# L289.net
KiCad netlist of a schematic drawn in EAGLE
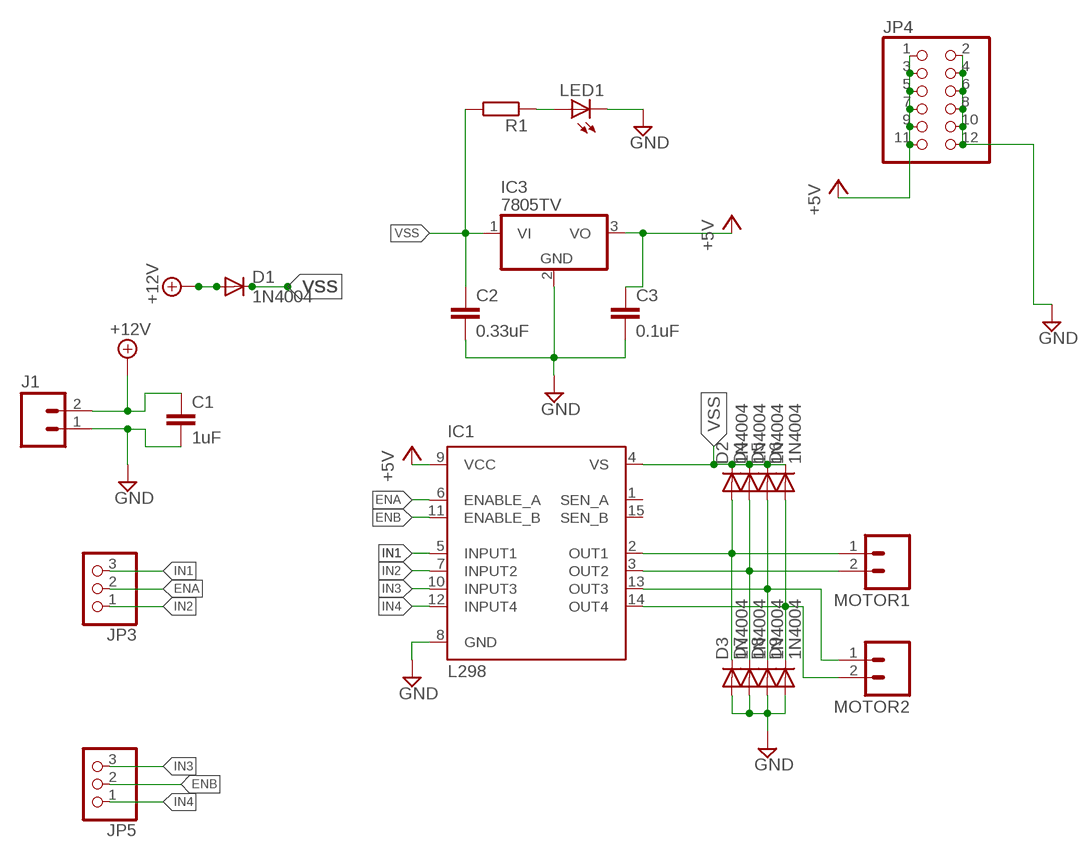
[diagram p0: schematic, sheet 1]

(export (version "E")
  (design (tool "Eeschema 10.0.6"))
  (components
    (comp (ref "C1")
      (value "1uF")
      (footprint "eagle-import:C050-024X044")
      (libsource (lib "eagle-import") (part "C-EU050-024X044"))
    )
    (comp (ref "C2")
      (value "0.33uF")
      (footprint "eagle-import:C050-024X044")
      (libsource (lib "eagle-import") (part "C-EU050-024X044"))
    )
    (comp (ref "C3")
      (value "0.1uF")
      (footprint "eagle-import:C050-024X044")
      (libsource (lib "eagle-import") (part "C-EU050-024X044"))
    )
    (comp (ref "D1")
      (value "1N4004")
      (footprint "eagle-import:DO41-10")
      (libsource (lib "eagle-import") (part "1N4004"))
    )
    (comp (ref "D2")
      (value "1N4004")
      (footprint "eagle-import:DO41-10")
      (libsource (lib "eagle-import") (part "1N4004"))
    )
    (comp (ref "D3")
      (value "1N4004")
      (footprint "eagle-import:DO41-10")
      (libsource (lib "eagle-import") (part "1N4004"))
    )
    (comp (ref "D4")
      (value "1N4004")
      (footprint "eagle-import:DO41-10")
      (libsource (lib "eagle-import") (part "1N4004"))
    )
    (comp (ref "D5")
      (value "1N4004")
      (footprint "eagle-import:DO41-10")
      (libsource (lib "eagle-import") (part "1N4004"))
    )
    (comp (ref "D6")
      (value "1N4004")
      (footprint "eagle-import:DO41-10")
      (libsource (lib "eagle-import") (part "1N4004"))
    )
    (comp (ref "D7")
      (value "1N4004")
      (footprint "eagle-import:DO41-10")
      (libsource (lib "eagle-import") (part "1N4004"))
    )
    (comp (ref "D8")
      (value "1N4004")
      (footprint "eagle-import:DO41-10")
      (libsource (lib "eagle-import") (part "1N4004"))
    )
    (comp (ref "D9")
      (value "1N4004")
      (footprint "eagle-import:DO41-10")
      (libsource (lib "eagle-import") (part "1N4004"))
    )
    (comp (ref "IC1")
      (value "L298")
      (footprint "eagle-import:MULTIWATT-15")
      (fields (field (name "MPN") "L298N"))
      (libsource (lib "eagle-import") (part "L298"))
    )
    (comp (ref "IC3")
      (value "7805TV")
      (footprint "eagle-import:TO220V")
      (libsource (lib "eagle-import") (part "78TV05"))
    )
    (comp (ref "J1")
      (value "M02-JST-2-PTH-NO_SILK")
      (footprint "eagle-import:JST-2-PTH-NS")
      (libsource (lib "eagle-import") (part "M02-JST-2-PTH-NO_SILK"))
    )
    (comp (ref "JP3")
      (value "PINHD-1X3")
      (footprint "eagle-import:1X03")
      (libsource (lib "eagle-import") (part "PINHD-1X3"))
    )
    (comp (ref "JP4")
      (value "PINHD-2X6")
      (footprint "eagle-import:2X06")
      (libsource (lib "eagle-import") (part "PINHD-2X6"))
    )
    (comp (ref "JP5")
      (value "PINHD-1X3")
      (footprint "eagle-import:1X03")
      (libsource (lib "eagle-import") (part "PINHD-1X3"))
    )
    (comp (ref "LED1")
      (value "LED3MM")
      (footprint "eagle-import:LED3MM")
      (libsource (lib "eagle-import") (part "LED3MM"))
    )
    (comp (ref "MOTOR1")
      (value "M02-JST-2-PTH-NO_SILK")
      (footprint "eagle-import:JST-2-PTH-NS")
      (libsource (lib "eagle-import") (part "M02-JST-2-PTH-NO_SILK"))
    )
    (comp (ref "MOTOR2")
      (value "M02-JST-2-PTH-NO_SILK")
      (footprint "eagle-import:JST-2-PTH-NS")
      (libsource (lib "eagle-import") (part "M02-JST-2-PTH-NO_SILK"))
    )
    (comp (ref "R1")
      (value "R-EU_0207/5V")
      (footprint "eagle-import:0207_5V")
      (libsource (lib "eagle-import") (part "R-EU_0207/5V"))
    )
  )
  (nets
    (net (code "1") (name "+5V") (class "Default")
      (node (ref "C3") (pin "1") (pinfunction "1_1") (pintype "passive"))
      (node (ref "IC1") (pin "9") (pinfunction "VCC_9") (pintype "power_in"))
      (node (ref "IC3") (pin "3") (pinfunction "VO_3") (pintype "passive"))
      (node (ref "JP4") (pin "1") (pinfunction "1_1") (pintype "passive"))
      (node (ref "JP4") (pin "11") (pinfunction "11_11") (pintype "passive"))
      (node (ref "JP4") (pin "3") (pinfunction "3_3") (pintype "passive"))
      (node (ref "JP4") (pin "5") (pinfunction "5_5") (pintype "passive"))
      (node (ref "JP4") (pin "7") (pinfunction "7_7") (pintype "passive"))
      (node (ref "JP4") (pin "9") (pinfunction "9_9") (pintype "passive"))
    )
    (net (code "2") (name "+12V") (class "Default")
      (node (ref "C1") (pin "1") (pinfunction "1_1") (pintype "passive"))
      (node (ref "D1") (pin "A") (pinfunction "A_A") (pintype "passive"))
      (node (ref "J1") (pin "2") (pinfunction "2_2") (pintype "passive"))
    )
    (net (code "3") (name "ENA") (class "Default")
      (node (ref "IC1") (pin "6") (pinfunction "ENABLE_A_6") (pintype "input"))
      (node (ref "JP3") (pin "2") (pinfunction "2_2") (pintype "passive"))
    )
    (net (code "4") (name "ENB") (class "Default")
      (node (ref "IC1") (pin "11") (pinfunction "ENABLE_B_11") (pintype "input"))
      (node (ref "JP5") (pin "2") (pinfunction "2_2") (pintype "passive"))
    )
    (net (code "5") (name "GND") (class "Default")
      (node (ref "C1") (pin "2") (pinfunction "2_2") (pintype "passive"))
      (node (ref "C2") (pin "2") (pinfunction "2_2") (pintype "passive"))
      (node (ref "C3") (pin "2") (pinfunction "2_2") (pintype "passive"))
      (node (ref "D3") (pin "A") (pinfunction "A_A") (pintype "passive"))
      (node (ref "D7") (pin "A") (pinfunction "A_A") (pintype "passive"))
      (node (ref "D8") (pin "A") (pinfunction "A_A") (pintype "passive"))
      (node (ref "D9") (pin "A") (pinfunction "A_A") (pintype "passive"))
      (node (ref "IC1") (pin "8") (pinfunction "GND_8") (pintype "power_in"))
      (node (ref "IC3") (pin "2") (pinfunction "GND_2") (pintype "passive"))
      (node (ref "J1") (pin "1") (pinfunction "1_1") (pintype "passive"))
      (node (ref "JP4") (pin "10") (pinfunction "10_10") (pintype "passive"))
      (node (ref "JP4") (pin "12") (pinfunction "12_12") (pintype "passive"))
      (node (ref "JP4") (pin "2") (pinfunction "2_2") (pintype "passive"))
      (node (ref "JP4") (pin "4") (pinfunction "4_4") (pintype "passive"))
      (node (ref "JP4") (pin "6") (pinfunction "6_6") (pintype "passive"))
      (node (ref "JP4") (pin "8") (pinfunction "8_8") (pintype "passive"))
      (node (ref "LED1") (pin "K") (pinfunction "C_K") (pintype "passive"))
    )
    (net (code "6") (name "IN1") (class "Default")
      (node (ref "IC1") (pin "5") (pinfunction "INPUT1_5") (pintype "input"))
      (node (ref "JP3") (pin "3") (pinfunction "3_3") (pintype "passive"))
    )
    (net (code "7") (name "IN2") (class "Default")
      (node (ref "IC1") (pin "7") (pinfunction "INPUT2_7") (pintype "input"))
      (node (ref "JP3") (pin "1") (pinfunction "1_1") (pintype "passive"))
    )
    (net (code "8") (name "IN3") (class "Default")
      (node (ref "IC1") (pin "10") (pinfunction "INPUT3_10") (pintype "input"))
      (node (ref "JP5") (pin "3") (pinfunction "3_3") (pintype "passive"))
    )
    (net (code "9") (name "IN4") (class "Default")
      (node (ref "IC1") (pin "12") (pinfunction "INPUT4_12") (pintype "input"))
      (node (ref "JP5") (pin "1") (pinfunction "1_1") (pintype "passive"))
    )
    (net (code "10") (name "Net-(IC1-OUT1)") (class "Default")
      (node (ref "D2") (pin "A") (pinfunction "A_A") (pintype "passive"))
      (node (ref "D3") (pin "C") (pinfunction "C_C") (pintype "passive"))
      (node (ref "IC1") (pin "2") (pinfunction "OUT1_2") (pintype "output"))
      (node (ref "MOTOR1") (pin "1") (pinfunction "1_1") (pintype "passive"))
    )
    (net (code "11") (name "Net-(IC1-OUT2)") (class "Default")
      (node (ref "D4") (pin "A") (pinfunction "A_A") (pintype "passive"))
      (node (ref "D7") (pin "C") (pinfunction "C_C") (pintype "passive"))
      (node (ref "IC1") (pin "3") (pinfunction "OUT2_3") (pintype "output"))
      (node (ref "MOTOR1") (pin "2") (pinfunction "2_2") (pintype "passive"))
    )
    (net (code "12") (name "Net-(IC1-OUT3)") (class "Default")
      (node (ref "D5") (pin "A") (pinfunction "A_A") (pintype "passive"))
      (node (ref "D8") (pin "C") (pinfunction "C_C") (pintype "passive"))
      (node (ref "IC1") (pin "13") (pinfunction "OUT3_13") (pintype "output"))
      (node (ref "MOTOR2") (pin "1") (pinfunction "1_1") (pintype "passive"))
    )
    (net (code "13") (name "Net-(IC1-OUT4)") (class "Default")
      (node (ref "D6") (pin "A") (pinfunction "A_A") (pintype "passive"))
      (node (ref "D9") (pin "C") (pinfunction "C_C") (pintype "passive"))
      (node (ref "IC1") (pin "14") (pinfunction "OUT4_14") (pintype "output"))
      (node (ref "MOTOR2") (pin "2") (pinfunction "2_2") (pintype "passive"))
    )
    (net (code "14") (name "Net-(LED1-PadA)") (class "Default")
      (node (ref "LED1") (pin "A") (pinfunction "A_A") (pintype "passive"))
      (node (ref "R1") (pin "1") (pinfunction "1_1") (pintype "passive"))
    )
    (net (code "15") (name "VSS") (class "Default")
      (node (ref "C2") (pin "1") (pinfunction "1_1") (pintype "passive"))
      (node (ref "D1") (pin "C") (pinfunction "C_C") (pintype "passive"))
      (node (ref "D2") (pin "C") (pinfunction "C_C") (pintype "passive"))
      (node (ref "D4") (pin "C") (pinfunction "C_C") (pintype "passive"))
      (node (ref "D5") (pin "C") (pinfunction "C_C") (pintype "passive"))
      (node (ref "D6") (pin "C") (pinfunction "C_C") (pintype "passive"))
      (node (ref "IC1") (pin "4") (pinfunction "VS_4") (pintype "power_in"))
      (node (ref "IC3") (pin "1") (pinfunction "VI_1") (pintype "input"))
      (node (ref "R1") (pin "2") (pinfunction "2_2") (pintype "passive"))
    )
    (net (code "16") (name "unconnected-(IC1-SEN_A-Pad1)") (class "Default")
      (node (ref "IC1") (pin "1") (pinfunction "SEN_A_1") (pintype "input"))
    )
    (net (code "17") (name "unconnected-(IC1-SEN_B-Pad15)") (class "Default")
      (node (ref "IC1") (pin "15") (pinfunction "SEN_B_15") (pintype "input"))
    )
  )
)
